# YL203_2084.net
KiCad netlist of a schematic drawn in Altium Designer
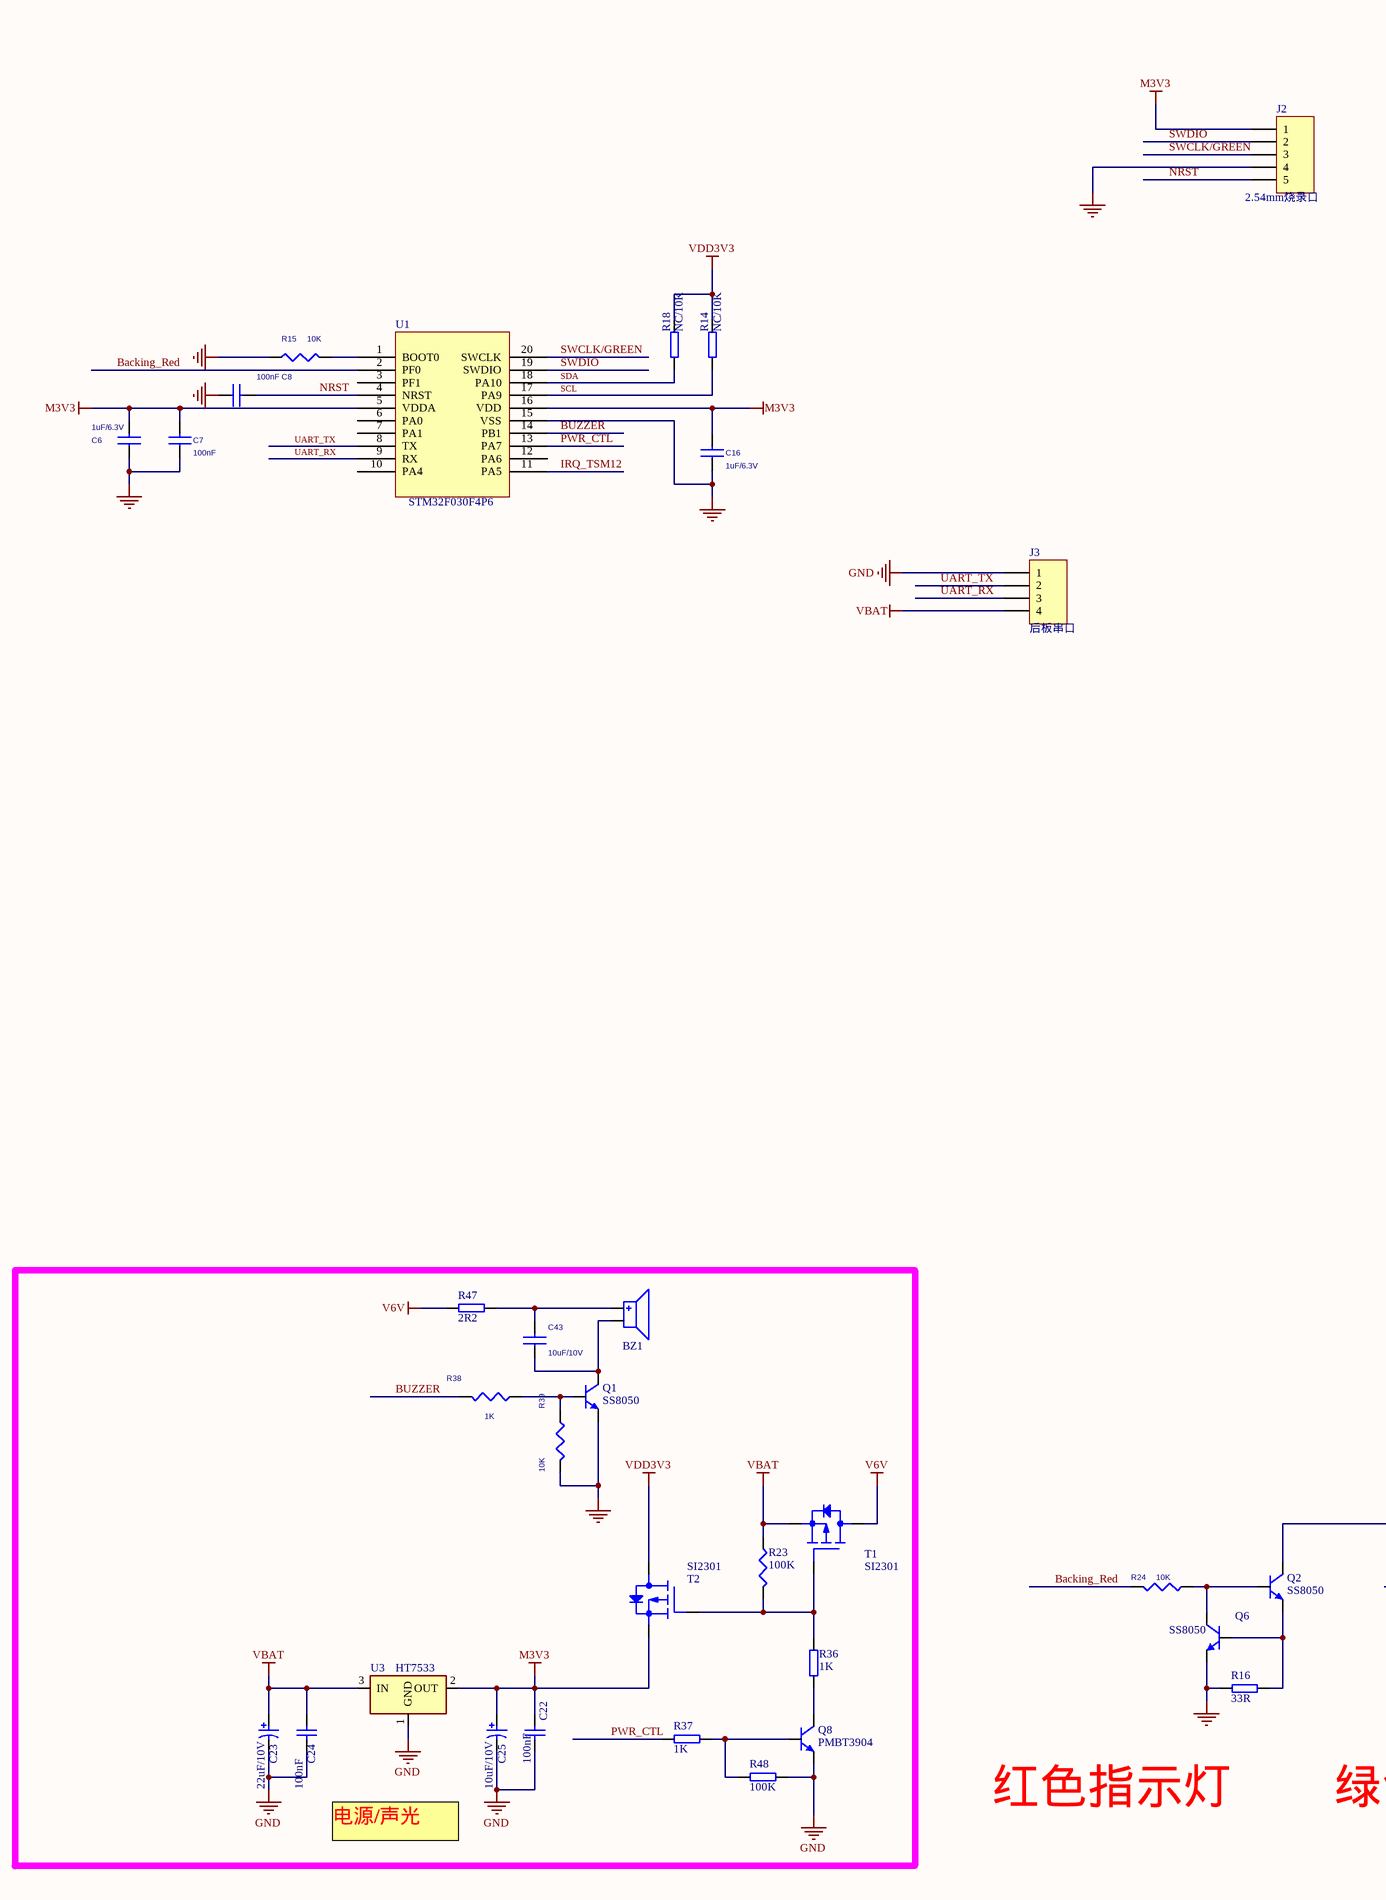
[diagram p0: YL203纯密码板2084.SchDoc, left]
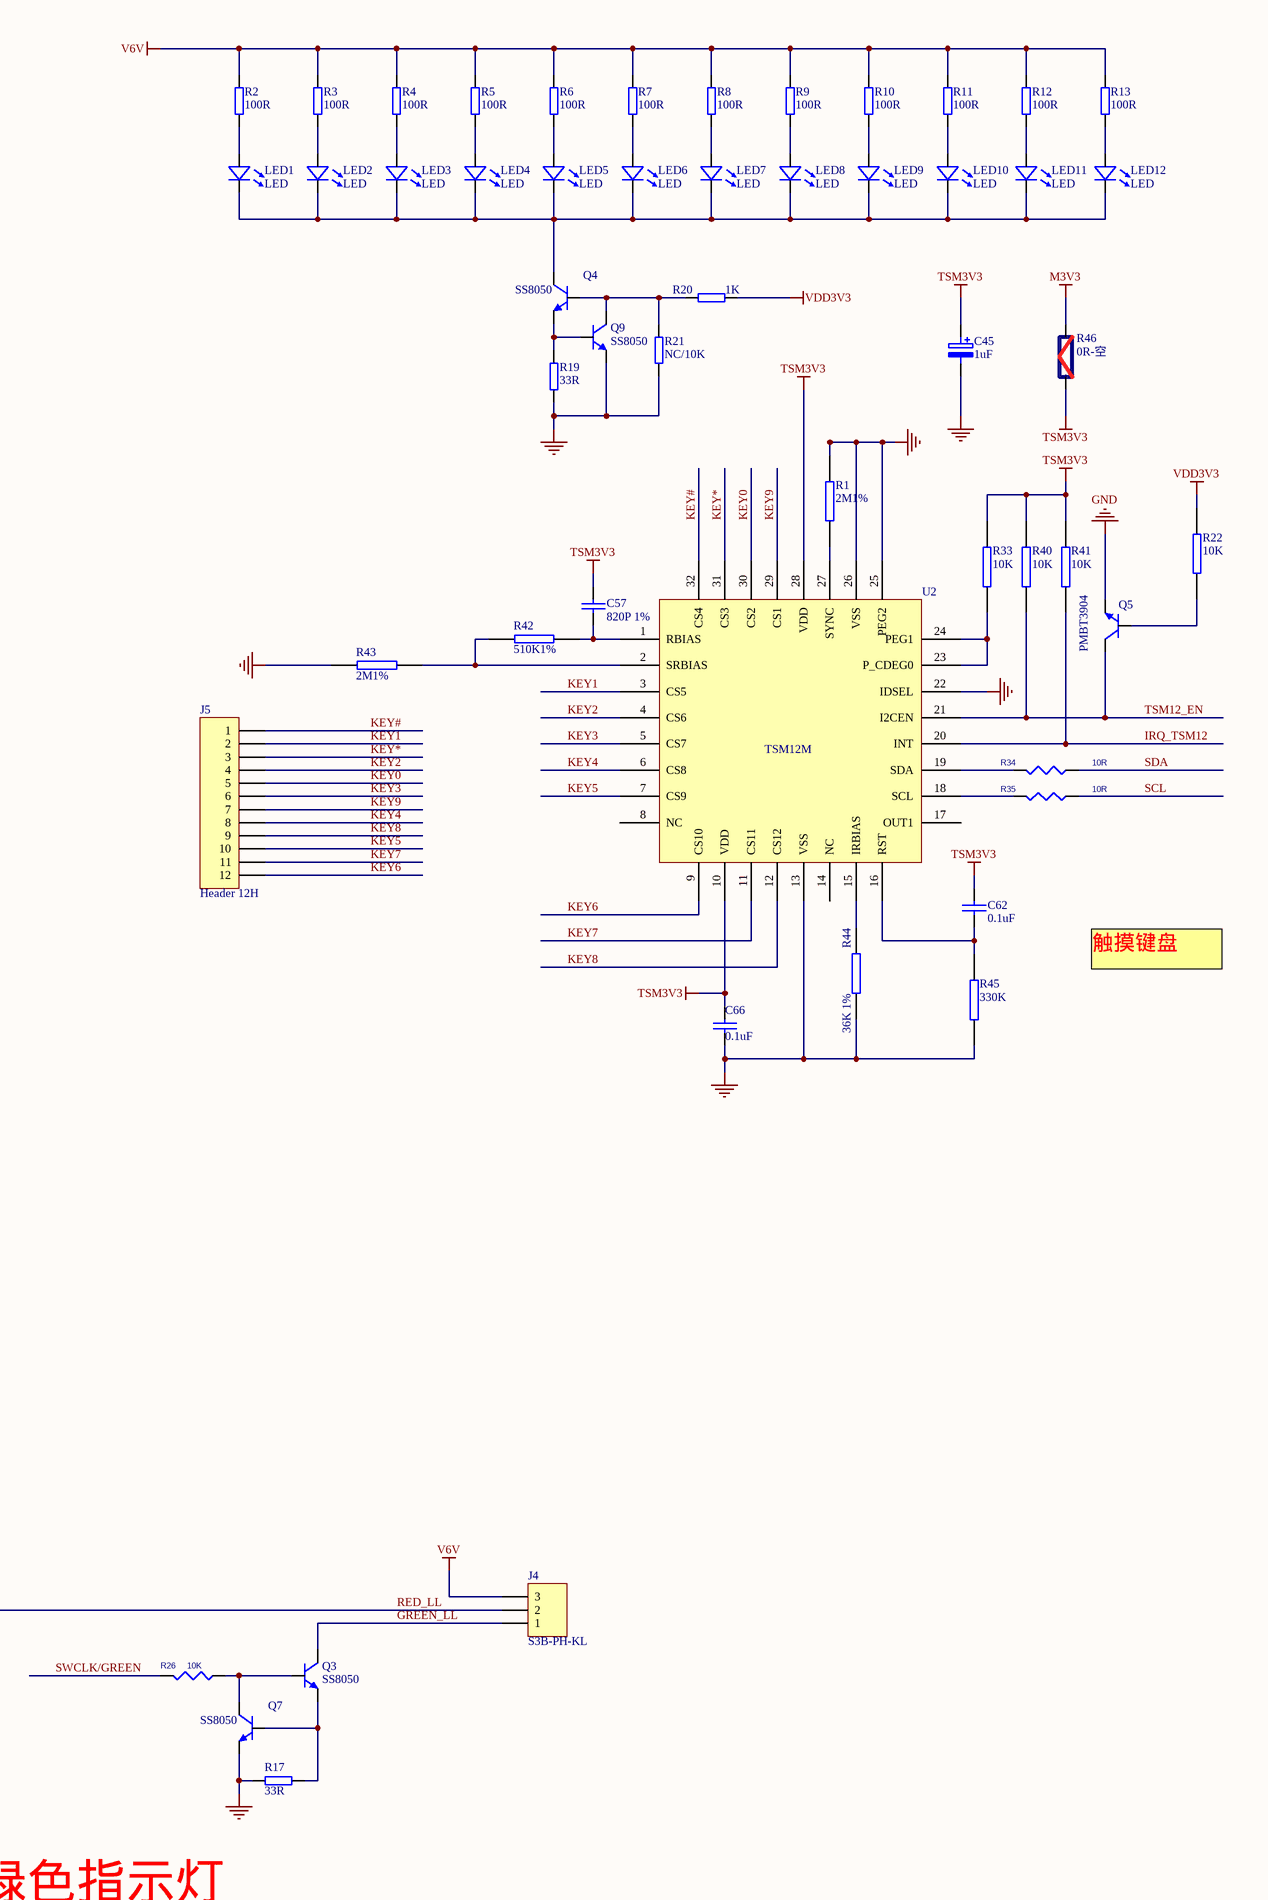
[diagram p1: YL203纯密码板2084.SchDoc, right]

(export (version "E")
  (design (tool "Eeschema 10.0.6"))
  (components
    (comp (ref "BZ1")
      (value "BUZZER")
      (footprint "BUZZER_D93_L40")
      (description "Buzzer")
      (libsource (lib "MyLibrary") (part "BUZZER"))
    )
    (comp (ref "C6") (value "1uF/6.3V") (footprint "LC-0603_C") (libsource (lib "*") (part "CAP NP")))
    (comp (ref "C7") (value "100nF") (footprint "LC-0603_C") (libsource (lib "*") (part "CAP NP")))
    (comp (ref "C8") (value "100nF") (footprint "LC-0603_C") (libsource (lib "*") (part "CAP NP")))
    (comp (ref "C16") (value "1uF/6.3V") (footprint "LC-0603_C") (libsource (lib "*") (part "CAP NP")))
    (comp (ref "C22")
      (value "100nF")
      (footprint "LC-0603_C")
      (description "Capacitor, Ceramic")
      (fields (field (name "TOLERANCE") "5 %"))
      (libsource (lib "MyLibrary") (part "CAP-NP"))
    )
    (comp (ref "C23")
      (value "22uF/10V")
      (footprint "LC-0805_C")
      (description "Capacitor, tolerance ±20%")
      (libsource (lib "MySchLib") (part "CAP-P"))
    )
    (comp (ref "C24")
      (value "100nF")
      (footprint "LC-0603_C")
      (description "Capacitor, Ceramic")
      (fields (field (name "TOLERANCE") "5 %"))
      (libsource (lib "MyLibrary") (part "CAP-NP"))
    )
    (comp (ref "C25")
      (value "10uF/10V")
      (footprint "LC-0805_C")
      (description "Capacitor, tolerance ±20%")
      (libsource (lib "MySchLib") (part "CAP-P"))
    )
    (comp (ref "C43") (value "10uF/10V") (footprint "LC-0603_C") (libsource (lib "*") (part "C_0_Dup1")))
    (comp (ref "C45")
      (value "1uF")
      (footprint "LC-0603_C")
      (description "Electrolytic Capacitor")
      (libsource (lib "*") (part "C-C型"))
    )
    (comp (ref "C57")
      (value "820P 1%")
      (footprint "LC-0402_C")
      (description "Capacitor")
      (libsource (lib "*") (part "CAP"))
    )
    (comp (ref "C62")
      (value "0.1uF")
      (footprint "LC-0603_C")
      (description "Capacitor")
      (libsource (lib "*") (part "CAP"))
    )
    (comp (ref "C66")
      (value "0.1uF")
      (footprint "LC-0402_C")
      (description "Capacitor")
      (libsource (lib "*") (part "CAP"))
    )
    (comp (ref "J2")
      (value "2.54mm烧录口")
      (footprint "5P-2.54mm")
      (description "Header, 5-Pin")
      (fields (field (name "PUBLISHER") "Altium Limited"))
      (libsource (lib "*") (part "Header 5"))
    )
    (comp (ref "J3")
      (value "后板串口")
      (footprint "4P-2.0XX")
      (description "Header, 4-Pin, Right Angle")
      (fields (field (name "PUBLISHER") "Altium Limited"))
      (libsource (lib "Miscellaneous Connectors") (part "Header 4H"))
    )
    (comp (ref "J4")
      (value "S3B-PH-KL")
      (footprint "3P-1.25mm-SMT")
      (description "Header, 3-Pin")
      (fields (field (name "PUBLISHER") "Altium Limited"))
      (libsource (lib "Miscellaneous Connectors") (part "Header 3"))
    )
    (comp (ref "J5")
      (value "Header 12H")
      (footprint "6P*2*1.27MM_1")
      (description "Header, 12-Pin, Right Angle")
      (fields (field (name "PUBLISHER") "Altium Limited"))
      (libsource (lib "Miscellaneous Connectors") (part "Header 12H"))
    )
    (comp (ref "LED1") (value "LED") (footprint "0603LED") (libsource (lib "MyLibrary") (part "LED")))
    (comp (ref "LED2") (value "LED") (footprint "0603LED") (libsource (lib "MyLibrary") (part "LED")))
    (comp (ref "LED3") (value "LED") (footprint "0603LED") (libsource (lib "MyLibrary") (part "LED")))
    (comp (ref "LED4") (value "LED") (footprint "0603LED") (libsource (lib "MyLibrary") (part "LED")))
    (comp (ref "LED5") (value "LED") (footprint "0603LED") (libsource (lib "MyLibrary") (part "LED")))
    (comp (ref "LED6") (value "LED") (footprint "0603LED") (libsource (lib "MyLibrary") (part "LED")))
    (comp (ref "LED7") (value "LED") (footprint "0603LED") (libsource (lib "MyLibrary") (part "LED")))
    (comp (ref "LED8") (value "LED") (footprint "0603LED") (libsource (lib "MyLibrary") (part "LED")))
    (comp (ref "LED9") (value "LED") (footprint "0603LED") (libsource (lib "MyLibrary") (part "LED")))
    (comp (ref "LED10") (value "LED") (footprint "0603LED") (libsource (lib "MyLibrary") (part "LED")))
    (comp (ref "LED11") (value "LED") (footprint "0603LED") (libsource (lib "MyLibrary") (part "LED")))
    (comp (ref "LED12") (value "LED") (footprint "0603LED") (libsource (lib "MyLibrary") (part "LED")))
    (comp (ref "Q1")
      (value "SS8050")
      (footprint "SOT-23-3L")
      (description "Bipolar Junction Transistor")
      (libsource (lib "MyLibrary") (part "NPN_BJT"))
    )
    (comp (ref "Q2")
      (value "SS8050")
      (footprint "SOT-23-3L")
      (description "Bipolar Junction Transistor")
      (libsource (lib "MyLibrary") (part "NPN_BJT"))
    )
    (comp (ref "Q3")
      (value "SS8050")
      (footprint "SOT-23-3L")
      (description "Bipolar Junction Transistor")
      (libsource (lib "MyLibrary") (part "NPN_BJT"))
    )
    (comp (ref "Q4")
      (value "SS8050")
      (footprint "SOT-23-3L")
      (description "Bipolar Junction Transistor")
      (libsource (lib "MyLibrary") (part "NPN_BJT"))
    )
    (comp (ref "Q5")
      (value "PMBT3904")
      (footprint "SOT-23-3L")
      (description "Bipolar Junction Transistor")
      (libsource (lib "MyLibrary") (part "NPN_BJT"))
    )
    (comp (ref "Q6")
      (value "SS8050")
      (footprint "SOT-23-3L")
      (description "Bipolar Junction Transistor")
      (libsource (lib "MyLibrary") (part "NPN_BJT"))
    )
    (comp (ref "Q7")
      (value "SS8050")
      (footprint "SOT-23-3L")
      (description "Bipolar Junction Transistor")
      (libsource (lib "MyLibrary") (part "NPN_BJT"))
    )
    (comp (ref "Q8")
      (value "PMBT3904")
      (footprint "SOT-23-3L")
      (description "Bipolar Junction Transistor")
      (libsource (lib "MyLibrary") (part "NPN_BJT"))
    )
    (comp (ref "Q9")
      (value "SS8050")
      (footprint "SOT-23-3L")
      (description "Bipolar Junction Transistor")
      (libsource (lib "MyLibrary") (part "NPN_BJT"))
    )
    (comp (ref "R1") (value "2M1%") (footprint "LC-0402_R") (libsource (lib "*") (part "RES2")))
    (comp (ref "R2") (value "100R") (footprint "LC-0603_R") (libsource (lib "MySch") (part "R")))
    (comp (ref "R3") (value "100R") (footprint "LC-0603_R") (libsource (lib "MySch") (part "R")))
    (comp (ref "R4") (value "100R") (footprint "LC-0603_R") (libsource (lib "MySch") (part "R")))
    (comp (ref "R5") (value "100R") (footprint "LC-0603_R") (libsource (lib "MySch") (part "R")))
    (comp (ref "R6") (value "100R") (footprint "LC-0603_R") (libsource (lib "MySch") (part "R")))
    (comp (ref "R7") (value "100R") (footprint "LC-0603_R") (libsource (lib "MySch") (part "R")))
    (comp (ref "R8") (value "100R") (footprint "LC-0603_R") (libsource (lib "MySch") (part "R")))
    (comp (ref "R9") (value "100R") (footprint "LC-0603_R") (libsource (lib "MySch") (part "R")))
    (comp (ref "R10") (value "100R") (footprint "LC-0603_R") (libsource (lib "MySch") (part "R")))
    (comp (ref "R11") (value "100R") (footprint "LC-0603_R") (libsource (lib "MySch") (part "R")))
    (comp (ref "R12") (value "100R") (footprint "LC-0603_R") (libsource (lib "MySch") (part "R")))
    (comp (ref "R13") (value "100R") (footprint "LC-0603_R") (libsource (lib "MySch") (part "R")))
    (comp (ref "R14") (value "NC/10K") (footprint "LC-0603_R") (libsource (lib "MySch") (part "R")))
    (comp (ref "R15") (value "10K") (footprint "LC-0603_R") (libsource (lib "*") (part "R_Dup1")))
    (comp (ref "R16") (value "33R") (footprint "LC-0603_R") (libsource (lib "MySch") (part "R")))
    (comp (ref "R17") (value "33R") (footprint "LC-0603_R") (libsource (lib "MySch") (part "R")))
    (comp (ref "R18") (value "NC/10K") (footprint "LC-0603_R") (libsource (lib "MySch") (part "R")))
    (comp (ref "R19") (value "33R") (footprint "LC-0603_R") (libsource (lib "MySch") (part "R")))
    (comp (ref "R20") (value "1K") (footprint "LC-0603_R") (libsource (lib "MySch") (part "R")))
    (comp (ref "R21") (value "NC/10K") (footprint "LC-0603_R") (libsource (lib "MySch") (part "R")))
    (comp (ref "R22") (value "10K") (footprint "LC-0603_R") (libsource (lib "*") (part "RES2")))
    (comp (ref "R23") (value "100K") (footprint "LC-0603_R") (libsource (lib "*") (part "R")))
    (comp (ref "R24") (value "10K") (footprint "LC-0603_R") (libsource (lib "*") (part "RES")))
    (comp (ref "R26") (value "10K") (footprint "LC-0603_R") (libsource (lib "*") (part "RES")))
    (comp (ref "R33") (value "10K") (footprint "LC-0402_R") (libsource (lib "*") (part "RES2")))
    (comp (ref "R34") (value "10R") (footprint "LC-0402_R") (libsource (lib "*") (part "R_Dup1")))
    (comp (ref "R35") (value "10R") (footprint "LC-0402_R") (libsource (lib "*") (part "R_Dup1")))
    (comp (ref "R36") (value "1K") (footprint "LC-0603_R") (libsource (lib "MySch") (part "R")))
    (comp (ref "R37") (value "1K") (footprint "LC-0603_R") (libsource (lib "MySch") (part "R")))
    (comp (ref "R38") (value "1K") (footprint "LC-0603_R") (libsource (lib "*") (part "R_Dup1")))
    (comp (ref "R39") (value "10K") (footprint "LC-0603_R") (libsource (lib "*") (part "R_Dup1")))
    (comp (ref "R40") (value "10K") (footprint "LC-0402_R") (libsource (lib "*") (part "RES2")))
    (comp (ref "R41") (value "10K") (footprint "LC-0402_R") (libsource (lib "*") (part "RES2")))
    (comp (ref "R42") (value "510K1%") (footprint "LC-0402_R") (libsource (lib "*") (part "RES2")))
    (comp (ref "R43") (value "2M1%") (footprint "LC-0402_R") (libsource (lib "*") (part "RES2")))
    (comp (ref "R44") (value "36K 1%") (footprint "LC-0402_R") (libsource (lib "*") (part "RES2")))
    (comp (ref "R45") (value "330K") (footprint "LC-0402_R") (libsource (lib "*") (part "RES2")))
    (comp (ref "R46") (value "0R-空") (footprint "LC-0603_R") (libsource (lib "MYSchlib") (part "POWER-R")))
    (comp (ref "R47") (value "2R2") (footprint "LC-0603_R") (libsource (lib "MySch") (part "R")))
    (comp (ref "R48") (value "100K") (footprint "LC-0603_R") (libsource (lib "MySch") (part "R")))
    (comp (ref "T1")
      (value "SI2301")
      (footprint "SOT-23 - GDS")
      (libsource (lib "*") (part "PWRMOSFET_EP_DGS_0"))
    )
    (comp (ref "T2")
      (value "SI2301")
      (footprint "SOT-23 - GDS")
      (libsource (lib "*") (part "PWRMOSFET_EP_DGS_0"))
    )
    (comp (ref "U1")
      (value "STM32F030F4P6")
      (footprint "TSSOP-20-0.66")
      (libsource (lib "*") (part "Component_1"))
    )
    (comp (ref "U2") (value "TSM12M") (footprint "ADS_TMS12") (libsource (lib "*") (part "TSM12M")))
    (comp (ref "U3") (value "HT7533") (footprint "SOT-23-3L") (libsource (lib "*") (part "XC6206P302M")))
  )
  (nets
    (net (code "1") (name "/BUZZER") (class "Default")
      (node (ref "R38") (pin "2") (pinfunction "2_2") (pintype "passive"))
      (node (ref "U1") (pin "14") (pinfunction "PB1_14") (pintype "passive"))
    )
    (net (code "2") (name "/Backing_Red") (class "Default")
      (node (ref "R24") (pin "2") (pinfunction "2_2") (pintype "passive"))
      (node (ref "U1") (pin "2") (pinfunction "PF0_2") (pintype "passive"))
    )
    (net (code "3") (name "/GREEN_LL") (class "Default")
      (node (ref "J4") (pin "1") (pinfunction "1_1") (pintype "passive"))
      (node (ref "Q3") (pin "3") (pinfunction "3_3") (pintype "passive"))
    )
    (net (code "4") (name "/IRQ_TSM12") (class "Default")
      (node (ref "R41") (pin "1") (pinfunction "1_1") (pintype "passive"))
      (node (ref "U1") (pin "11") (pinfunction "PA5_11") (pintype "passive"))
      (node (ref "U2") (pin "20") (pinfunction "INT_20") (pintype "passive"))
    )
    (net (code "5") (name "/KEY#") (class "Default")
      (node (ref "J5") (pin "1") (pinfunction "1_1") (pintype "passive"))
      (node (ref "U2") (pin "32") (pinfunction "CS4_32") (pintype "passive"))
    )
    (net (code "6") (name "/KEY*") (class "Default")
      (node (ref "J5") (pin "3") (pinfunction "3_3") (pintype "passive"))
      (node (ref "U2") (pin "31") (pinfunction "CS3_31") (pintype "passive"))
    )
    (net (code "7") (name "/KEY0") (class "Default")
      (node (ref "J5") (pin "5") (pinfunction "5_5") (pintype "passive"))
      (node (ref "U2") (pin "30") (pinfunction "CS2_30") (pintype "passive"))
    )
    (net (code "8") (name "/KEY1") (class "Default")
      (node (ref "J5") (pin "2") (pinfunction "2_2") (pintype "passive"))
      (node (ref "U2") (pin "3") (pinfunction "CS5_3") (pintype "passive"))
    )
    (net (code "9") (name "/KEY2") (class "Default")
      (node (ref "J5") (pin "4") (pinfunction "4_4") (pintype "passive"))
      (node (ref "U2") (pin "4") (pinfunction "CS6_4") (pintype "passive"))
    )
    (net (code "10") (name "/KEY3") (class "Default")
      (node (ref "J5") (pin "6") (pinfunction "6_6") (pintype "passive"))
      (node (ref "U2") (pin "5") (pinfunction "CS7_5") (pintype "passive"))
    )
    (net (code "11") (name "/KEY4") (class "Default")
      (node (ref "J5") (pin "8") (pinfunction "8_8") (pintype "passive"))
      (node (ref "U2") (pin "6") (pinfunction "CS8_6") (pintype "passive"))
    )
    (net (code "12") (name "/KEY5") (class "Default")
      (node (ref "J5") (pin "10") (pinfunction "10_10") (pintype "passive"))
      (node (ref "U2") (pin "7") (pinfunction "CS9_7") (pintype "passive"))
    )
    (net (code "13") (name "/KEY6") (class "Default")
      (node (ref "J5") (pin "12") (pinfunction "12_12") (pintype "passive"))
      (node (ref "U2") (pin "9") (pinfunction "CS10_9") (pintype "passive"))
    )
    (net (code "14") (name "/KEY7") (class "Default")
      (node (ref "J5") (pin "11") (pinfunction "11_11") (pintype "passive"))
      (node (ref "U2") (pin "11") (pinfunction "CS11_11") (pintype "passive"))
    )
    (net (code "15") (name "/KEY8") (class "Default")
      (node (ref "J5") (pin "9") (pinfunction "9_9") (pintype "passive"))
      (node (ref "U2") (pin "12") (pinfunction "CS12_12") (pintype "passive"))
    )
    (net (code "16") (name "/KEY9") (class "Default")
      (node (ref "J5") (pin "7") (pinfunction "7_7") (pintype "passive"))
      (node (ref "U2") (pin "29") (pinfunction "CS1_29") (pintype "passive"))
    )
    (net (code "17") (name "/NRST") (class "Default")
      (node (ref "C8") (pin "2") (pinfunction "2_2") (pintype "passive"))
      (node (ref "J2") (pin "5") (pinfunction "5_5") (pintype "passive"))
      (node (ref "U1") (pin "4") (pinfunction "NRST_4") (pintype "passive"))
    )
    (net (code "18") (name "/PWR_CTL") (class "Default")
      (node (ref "R37") (pin "1") (pintype "passive"))
      (node (ref "U1") (pin "13") (pinfunction "PA7_13") (pintype "passive"))
    )
    (net (code "19") (name "/RED_LL") (class "Default")
      (node (ref "J4") (pin "2") (pinfunction "2_2") (pintype "passive"))
      (node (ref "Q2") (pin "3") (pinfunction "3_3") (pintype "passive"))
    )
    (net (code "20") (name "/SCL") (class "Default")
      (node (ref "R14") (pin "1") (pintype "passive"))
      (node (ref "R35") (pin "1") (pinfunction "1_1") (pintype "passive"))
      (node (ref "U1") (pin "17") (pinfunction "PA9_17") (pintype "passive"))
    )
    (net (code "21") (name "/SDA") (class "Default")
      (node (ref "R18") (pin "1") (pintype "passive"))
      (node (ref "R34") (pin "1") (pinfunction "1_1") (pintype "passive"))
      (node (ref "U1") (pin "18") (pinfunction "PA10_18") (pintype "passive"))
    )
    (net (code "22") (name "/SWCLK{slash}GREEN") (class "Default")
      (node (ref "J2") (pin "3") (pinfunction "3_3") (pintype "passive"))
      (node (ref "R26") (pin "2") (pinfunction "2_2") (pintype "passive"))
      (node (ref "U1") (pin "20") (pinfunction "SWCLK_20") (pintype "passive"))
    )
    (net (code "23") (name "/SWDIO") (class "Default")
      (node (ref "J2") (pin "2") (pinfunction "2_2") (pintype "passive"))
      (node (ref "U1") (pin "19") (pinfunction "SWDIO_19") (pintype "passive"))
    )
    (net (code "24") (name "/TSM12_EN") (class "Default")
      (node (ref "Q5") (pin "3") (pinfunction "3_3") (pintype "passive"))
      (node (ref "R40") (pin "1") (pinfunction "1_1") (pintype "passive"))
      (node (ref "U2") (pin "21") (pinfunction "I2CEN_21") (pintype "passive"))
    )
    (net (code "25") (name "/UART_RX") (class "Default")
      (node (ref "J3") (pin "3") (pinfunction "3_3") (pintype "passive"))
      (node (ref "U1") (pin "9") (pinfunction "RX_9") (pintype "passive"))
    )
    (net (code "26") (name "/UART_TX") (class "Default")
      (node (ref "J3") (pin "2") (pinfunction "2_2") (pintype "passive"))
      (node (ref "U1") (pin "8") (pinfunction "TX_8") (pintype "passive"))
    )
    (net (code "27") (name "GND") (class "Default")
      (node (ref "C16") (pin "1") (pinfunction "1_1") (pintype "passive"))
      (node (ref "C22") (pin "2") (pinfunction "2_2") (pintype "passive"))
      (node (ref "C23") (pin "2") (pinfunction "2_2") (pintype "passive"))
      (node (ref "C24") (pin "2") (pinfunction "2_2") (pintype "passive"))
      (node (ref "C25") (pin "2") (pinfunction "2_2") (pintype "passive"))
      (node (ref "C45") (pin "2") (pinfunction "2_2") (pintype "passive"))
      (node (ref "C6") (pin "1") (pinfunction "1_1") (pintype "passive"))
      (node (ref "C66") (pin "1") (pinfunction "1_1") (pintype "passive"))
      (node (ref "C7") (pin "1") (pinfunction "1_1") (pintype "passive"))
      (node (ref "C8") (pin "1") (pinfunction "1_1") (pintype "passive"))
      (node (ref "J2") (pin "4") (pinfunction "4_4") (pintype "passive"))
      (node (ref "J3") (pin "1") (pinfunction "1_1") (pintype "passive"))
      (node (ref "Q1") (pin "2") (pinfunction "2_2") (pintype "passive"))
      (node (ref "Q5") (pin "2") (pinfunction "2_2") (pintype "passive"))
      (node (ref "Q6") (pin "2") (pinfunction "2_2") (pintype "passive"))
      (node (ref "Q7") (pin "2") (pinfunction "2_2") (pintype "passive"))
      (node (ref "Q8") (pin "2") (pinfunction "2_2") (pintype "passive"))
      (node (ref "Q9") (pin "2") (pinfunction "2_2") (pintype "passive"))
      (node (ref "R1") (pin "2") (pinfunction "2_2") (pintype "passive"))
      (node (ref "R15") (pin "1") (pinfunction "1_1") (pintype "passive"))
      (node (ref "R16") (pin "2") (pintype "passive"))
      (node (ref "R17") (pin "2") (pintype "passive"))
      (node (ref "R19") (pin "1") (pintype "passive"))
      (node (ref "R21") (pin "1") (pintype "passive"))
      (node (ref "R39") (pin "2") (pinfunction "2_2") (pintype "passive"))
      (node (ref "R43") (pin "1") (pinfunction "1_1") (pintype "passive"))
      (node (ref "R44") (pin "1") (pinfunction "1_1") (pintype "passive"))
      (node (ref "R45") (pin "1") (pinfunction "1_1") (pintype "passive"))
      (node (ref "R48") (pin "1") (pintype "passive"))
      (node (ref "U1") (pin "15") (pinfunction "VSS_15") (pintype "passive"))
      (node (ref "U2") (pin "13") (pinfunction "VSS_13") (pintype "passive"))
      (node (ref "U2") (pin "22") (pinfunction "IDSEL_22") (pintype "passive"))
      (node (ref "U2") (pin "25") (pinfunction "PEG2_25") (pintype "passive"))
      (node (ref "U2") (pin "26") (pinfunction "VSS_26") (pintype "passive"))
      (node (ref "U3") (pin "1") (pinfunction "GND_1") (pintype "passive"))
    )
    (net (code "28") (name "M3V3") (class "Default")
      (node (ref "C16") (pin "2") (pinfunction "2_2") (pintype "passive"))
      (node (ref "C22") (pin "1") (pinfunction "1_1") (pintype "passive"))
      (node (ref "C25") (pin "1") (pinfunction "1_1") (pintype "passive"))
      (node (ref "C6") (pin "2") (pinfunction "2_2") (pintype "passive"))
      (node (ref "C7") (pin "2") (pinfunction "2_2") (pintype "passive"))
      (node (ref "J2") (pin "1") (pinfunction "1_1") (pintype "passive"))
      (node (ref "R46") (pin "2") (pinfunction "2_2") (pintype "passive"))
      (node (ref "T2") (pin "S") (pinfunction "SOURCE_S") (pintype "passive"))
      (node (ref "U1") (pin "16") (pinfunction "VDD_16") (pintype "passive"))
      (node (ref "U1") (pin "5") (pinfunction "VDDA_5") (pintype "passive"))
      (node (ref "U3") (pin "2") (pinfunction "OUT_2") (pintype "passive"))
    )
    (net (code "29") (name "Net-(BZ1-Pad1)") (class "Default")
      (node (ref "BZ1") (pin "1") (pintype "passive"))
      (node (ref "C43") (pin "2") (pinfunction "2_2") (pintype "passive"))
      (node (ref "R47") (pin "1") (pintype "passive"))
    )
    (net (code "30") (name "Net-(BZ1-Pad2)") (class "Default")
      (node (ref "BZ1") (pin "2") (pintype "passive"))
      (node (ref "C43") (pin "1") (pinfunction "1_1") (pintype "passive"))
      (node (ref "Q1") (pin "3") (pinfunction "3_3") (pintype "passive"))
    )
    (net (code "31") (name "Net-(LED1-a)") (class "Default")
      (node (ref "LED1") (pin "1") (pinfunction "a_1") (pintype "passive"))
      (node (ref "R2") (pin "1") (pintype "passive"))
    )
    (net (code "32") (name "Net-(LED1-k)") (class "Default")
      (node (ref "LED1") (pin "2") (pinfunction "k_2") (pintype "passive"))
      (node (ref "LED10") (pin "2") (pinfunction "k_2") (pintype "passive"))
      (node (ref "LED11") (pin "2") (pinfunction "k_2") (pintype "passive"))
      (node (ref "LED12") (pin "2") (pinfunction "k_2") (pintype "passive"))
      (node (ref "LED2") (pin "2") (pinfunction "k_2") (pintype "passive"))
      (node (ref "LED3") (pin "2") (pinfunction "k_2") (pintype "passive"))
      (node (ref "LED4") (pin "2") (pinfunction "k_2") (pintype "passive"))
      (node (ref "LED5") (pin "2") (pinfunction "k_2") (pintype "passive"))
      (node (ref "LED6") (pin "2") (pinfunction "k_2") (pintype "passive"))
      (node (ref "LED7") (pin "2") (pinfunction "k_2") (pintype "passive"))
      (node (ref "LED8") (pin "2") (pinfunction "k_2") (pintype "passive"))
      (node (ref "LED9") (pin "2") (pinfunction "k_2") (pintype "passive"))
      (node (ref "Q4") (pin "3") (pinfunction "3_3") (pintype "passive"))
    )
    (net (code "33") (name "Net-(LED2-a)") (class "Default")
      (node (ref "LED2") (pin "1") (pinfunction "a_1") (pintype "passive"))
      (node (ref "R3") (pin "1") (pintype "passive"))
    )
    (net (code "34") (name "Net-(LED3-a)") (class "Default")
      (node (ref "LED3") (pin "1") (pinfunction "a_1") (pintype "passive"))
      (node (ref "R4") (pin "1") (pintype "passive"))
    )
    (net (code "35") (name "Net-(LED4-a)") (class "Default")
      (node (ref "LED4") (pin "1") (pinfunction "a_1") (pintype "passive"))
      (node (ref "R5") (pin "1") (pintype "passive"))
    )
    (net (code "36") (name "Net-(LED5-a)") (class "Default")
      (node (ref "LED5") (pin "1") (pinfunction "a_1") (pintype "passive"))
      (node (ref "R6") (pin "1") (pintype "passive"))
    )
    (net (code "37") (name "Net-(LED6-a)") (class "Default")
      (node (ref "LED6") (pin "1") (pinfunction "a_1") (pintype "passive"))
      (node (ref "R7") (pin "1") (pintype "passive"))
    )
    (net (code "38") (name "Net-(LED7-a)") (class "Default")
      (node (ref "LED7") (pin "1") (pinfunction "a_1") (pintype "passive"))
      (node (ref "R8") (pin "1") (pintype "passive"))
    )
    (net (code "39") (name "Net-(LED8-a)") (class "Default")
      (node (ref "LED8") (pin "1") (pinfunction "a_1") (pintype "passive"))
      (node (ref "R9") (pin "1") (pintype "passive"))
    )
    (net (code "40") (name "Net-(LED9-a)") (class "Default")
      (node (ref "LED9") (pin "1") (pinfunction "a_1") (pintype "passive"))
      (node (ref "R10") (pin "1") (pintype "passive"))
    )
    (net (code "41") (name "Net-(LED10-a)") (class "Default")
      (node (ref "LED10") (pin "1") (pinfunction "a_1") (pintype "passive"))
      (node (ref "R11") (pin "1") (pintype "passive"))
    )
    (net (code "42") (name "Net-(LED11-a)") (class "Default")
      (node (ref "LED11") (pin "1") (pinfunction "a_1") (pintype "passive"))
      (node (ref "R12") (pin "1") (pintype "passive"))
    )
    (net (code "43") (name "Net-(LED12-a)") (class "Default")
      (node (ref "LED12") (pin "1") (pinfunction "a_1") (pintype "passive"))
      (node (ref "R13") (pin "1") (pintype "passive"))
    )
    (net (code "44") (name "Net-(Q1-Pad1)") (class "Default")
      (node (ref "Q1") (pin "1") (pinfunction "1_1") (pintype "passive"))
      (node (ref "R38") (pin "1") (pinfunction "1_1") (pintype "passive"))
      (node (ref "R39") (pin "1") (pinfunction "1_1") (pintype "passive"))
    )
    (net (code "45") (name "Net-(Q2-Pad1)") (class "Default")
      (node (ref "Q2") (pin "1") (pinfunction "1_1") (pintype "passive"))
      (node (ref "Q6") (pin "3") (pinfunction "3_3") (pintype "passive"))
      (node (ref "R24") (pin "1") (pinfunction "1_1") (pintype "passive"))
    )
    (net (code "46") (name "Net-(Q2-Pad2)") (class "Default")
      (node (ref "Q2") (pin "2") (pinfunction "2_2") (pintype "passive"))
      (node (ref "Q6") (pin "1") (pinfunction "1_1") (pintype "passive"))
      (node (ref "R16") (pin "1") (pintype "passive"))
    )
    (net (code "47") (name "Net-(Q3-Pad1)") (class "Default")
      (node (ref "Q3") (pin "1") (pinfunction "1_1") (pintype "passive"))
      (node (ref "Q7") (pin "3") (pinfunction "3_3") (pintype "passive"))
      (node (ref "R26") (pin "1") (pinfunction "1_1") (pintype "passive"))
    )
    (net (code "48") (name "Net-(Q3-Pad2)") (class "Default")
      (node (ref "Q3") (pin "2") (pinfunction "2_2") (pintype "passive"))
      (node (ref "Q7") (pin "1") (pinfunction "1_1") (pintype "passive"))
      (node (ref "R17") (pin "1") (pintype "passive"))
    )
    (net (code "49") (name "Net-(Q4-Pad1)") (class "Default")
      (node (ref "Q4") (pin "1") (pinfunction "1_1") (pintype "passive"))
      (node (ref "Q9") (pin "3") (pinfunction "3_3") (pintype "passive"))
      (node (ref "R20") (pin "1") (pintype "passive"))
      (node (ref "R21") (pin "2") (pintype "passive"))
    )
    (net (code "50") (name "Net-(Q4-Pad2)") (class "Default")
      (node (ref "Q4") (pin "2") (pinfunction "2_2") (pintype "passive"))
      (node (ref "Q9") (pin "1") (pinfunction "1_1") (pintype "passive"))
      (node (ref "R19") (pin "2") (pintype "passive"))
    )
    (net (code "51") (name "Net-(Q5-Pad1)") (class "Default")
      (node (ref "Q5") (pin "1") (pinfunction "1_1") (pintype "passive"))
      (node (ref "R22") (pin "1") (pinfunction "1_1") (pintype "passive"))
    )
    (net (code "52") (name "Net-(Q8-Pad1)") (class "Default")
      (node (ref "Q8") (pin "1") (pinfunction "1_1") (pintype "passive"))
      (node (ref "R37") (pin "2") (pintype "passive"))
      (node (ref "R48") (pin "2") (pintype "passive"))
    )
    (net (code "53") (name "Net-(Q8-Pad3)") (class "Default")
      (node (ref "Q8") (pin "3") (pinfunction "3_3") (pintype "passive"))
      (node (ref "R36") (pin "2") (pintype "passive"))
    )
    (net (code "54") (name "Net-(T1-GATE)") (class "Default")
      (node (ref "R23") (pin "2") (pinfunction "2_2") (pintype "passive"))
      (node (ref "R36") (pin "1") (pintype "passive"))
      (node (ref "T1") (pin "G") (pinfunction "GATE_G") (pintype "passive"))
      (node (ref "T2") (pin "G") (pinfunction "GATE_G") (pintype "passive"))
    )
    (net (code "55") (name "Net-(U1-BOOT0)") (class "Default")
      (node (ref "R15") (pin "2") (pinfunction "2_2") (pintype "passive"))
      (node (ref "U1") (pin "1") (pinfunction "BOOT0_1") (pintype "passive"))
    )
    (net (code "56") (name "Net-(U2-IRBIAS)") (class "Default")
      (node (ref "R44") (pin "2") (pinfunction "2_2") (pintype "passive"))
      (node (ref "U2") (pin "15") (pinfunction "IRBIAS_15") (pintype "passive"))
    )
    (net (code "57") (name "Net-(U2-PEG1)") (class "Default")
      (node (ref "R33") (pin "1") (pinfunction "1_1") (pintype "passive"))
      (node (ref "U2") (pin "23") (pinfunction "P_CDEG0_23") (pintype "passive"))
      (node (ref "U2") (pin "24") (pinfunction "PEG1_24") (pintype "passive"))
    )
    (net (code "58") (name "Net-(U2-RBIAS)") (class "Default")
      (node (ref "C57") (pin "1") (pinfunction "1_1") (pintype "passive"))
      (node (ref "R42") (pin "2") (pinfunction "2_2") (pintype "passive"))
      (node (ref "U2") (pin "1") (pinfunction "RBIAS_1") (pintype "passive"))
    )
    (net (code "59") (name "Net-(U2-RST)") (class "Default")
      (node (ref "C62") (pin "1") (pinfunction "1_1") (pintype "passive"))
      (node (ref "R45") (pin "2") (pinfunction "2_2") (pintype "passive"))
      (node (ref "U2") (pin "16") (pinfunction "RST_16") (pintype "passive"))
    )
    (net (code "60") (name "Net-(U2-SCL)") (class "Default")
      (node (ref "R35") (pin "2") (pinfunction "2_2") (pintype "passive"))
      (node (ref "U2") (pin "18") (pinfunction "SCL_18") (pintype "passive"))
    )
    (net (code "61") (name "Net-(U2-SDA)") (class "Default")
      (node (ref "R34") (pin "2") (pinfunction "2_2") (pintype "passive"))
      (node (ref "U2") (pin "19") (pinfunction "SDA_19") (pintype "passive"))
    )
    (net (code "62") (name "Net-(U2-SRBIAS)") (class "Default")
      (node (ref "R42") (pin "1") (pinfunction "1_1") (pintype "passive"))
      (node (ref "R43") (pin "2") (pinfunction "2_2") (pintype "passive"))
      (node (ref "U2") (pin "2") (pinfunction "SRBIAS_2") (pintype "passive"))
    )
    (net (code "63") (name "Net-(U2-SYNC)") (class "Default")
      (node (ref "R1") (pin "1") (pinfunction "1_1") (pintype "passive"))
      (node (ref "U2") (pin "27") (pinfunction "SYNC_27") (pintype "passive"))
    )
    (net (code "64") (name "TSM3V3") (class "Default")
      (node (ref "C45") (pin "1") (pinfunction "1_1") (pintype "passive"))
      (node (ref "C57") (pin "2") (pinfunction "2_2") (pintype "passive"))
      (node (ref "C62") (pin "2") (pinfunction "2_2") (pintype "passive"))
      (node (ref "C66") (pin "2") (pinfunction "2_2") (pintype "passive"))
      (node (ref "R33") (pin "2") (pinfunction "2_2") (pintype "passive"))
      (node (ref "R40") (pin "2") (pinfunction "2_2") (pintype "passive"))
      (node (ref "R41") (pin "2") (pinfunction "2_2") (pintype "passive"))
      (node (ref "R46") (pin "1") (pinfunction "1_1") (pintype "passive"))
      (node (ref "U2") (pin "10") (pinfunction "VDD_10") (pintype "passive"))
      (node (ref "U2") (pin "28") (pinfunction "VDD_28") (pintype "passive"))
    )
    (net (code "65") (name "V6V") (class "Default")
      (node (ref "J4") (pin "3") (pinfunction "3_3") (pintype "passive"))
      (node (ref "R10") (pin "2") (pintype "passive"))
      (node (ref "R11") (pin "2") (pintype "passive"))
      (node (ref "R12") (pin "2") (pintype "passive"))
      (node (ref "R13") (pin "2") (pintype "passive"))
      (node (ref "R2") (pin "2") (pintype "passive"))
      (node (ref "R3") (pin "2") (pintype "passive"))
      (node (ref "R4") (pin "2") (pintype "passive"))
      (node (ref "R47") (pin "2") (pintype "passive"))
      (node (ref "R5") (pin "2") (pintype "passive"))
      (node (ref "R6") (pin "2") (pintype "passive"))
      (node (ref "R7") (pin "2") (pintype "passive"))
      (node (ref "R8") (pin "2") (pintype "passive"))
      (node (ref "R9") (pin "2") (pintype "passive"))
      (node (ref "T1") (pin "D") (pinfunction "DRAIN_D") (pintype "passive"))
    )
    (net (code "66") (name "VBAT") (class "Default")
      (node (ref "C23") (pin "1") (pinfunction "1_1") (pintype "passive"))
      (node (ref "C24") (pin "1") (pinfunction "1_1") (pintype "passive"))
      (node (ref "J3") (pin "4") (pinfunction "4_4") (pintype "passive"))
      (node (ref "R23") (pin "1") (pinfunction "1_1") (pintype "passive"))
      (node (ref "T1") (pin "S") (pinfunction "SOURCE_S") (pintype "passive"))
      (node (ref "U3") (pin "3") (pinfunction "IN_3") (pintype "passive"))
    )
    (net (code "67") (name "VDD3V3") (class "Default")
      (node (ref "R14") (pin "2") (pintype "passive"))
      (node (ref "R18") (pin "2") (pintype "passive"))
      (node (ref "R20") (pin "2") (pintype "passive"))
      (node (ref "R22") (pin "2") (pinfunction "2_2") (pintype "passive"))
      (node (ref "T2") (pin "D") (pinfunction "DRAIN_D") (pintype "passive"))
    )
    (net (code "68") (name "unconnected-(U1-PA0-Pad6)") (class "Default")
      (node (ref "U1") (pin "6") (pinfunction "PA0_6") (pintype "passive"))
    )
    (net (code "69") (name "unconnected-(U1-PA1-Pad7)") (class "Default")
      (node (ref "U1") (pin "7") (pinfunction "PA1_7") (pintype "passive"))
    )
    (net (code "70") (name "unconnected-(U1-PA4-Pad10)") (class "Default")
      (node (ref "U1") (pin "10") (pinfunction "PA4_10") (pintype "passive"))
    )
    (net (code "71") (name "unconnected-(U1-PA6-Pad12)") (class "Default")
      (node (ref "U1") (pin "12") (pinfunction "PA6_12") (pintype "passive"))
    )
    (net (code "72") (name "unconnected-(U1-PF1-Pad3)") (class "Default")
      (node (ref "U1") (pin "3") (pinfunction "PF1_3") (pintype "passive"))
    )
    (net (code "73") (name "unconnected-(U2-NC-Pad8)") (class "Default")
      (node (ref "U2") (pin "8") (pinfunction "NC_8") (pintype "passive"))
    )
    (net (code "74") (name "unconnected-(U2-NC-Pad14)") (class "Default")
      (node (ref "U2") (pin "14") (pinfunction "NC_14") (pintype "passive"))
    )
    (net (code "75") (name "unconnected-(U2-OUT1-Pad17)") (class "Default")
      (node (ref "U2") (pin "17") (pinfunction "OUT1_17") (pintype "passive"))
    )
  )
)
